# Cymbals.net
KiCad netlist of a schematic drawn in EAGLE
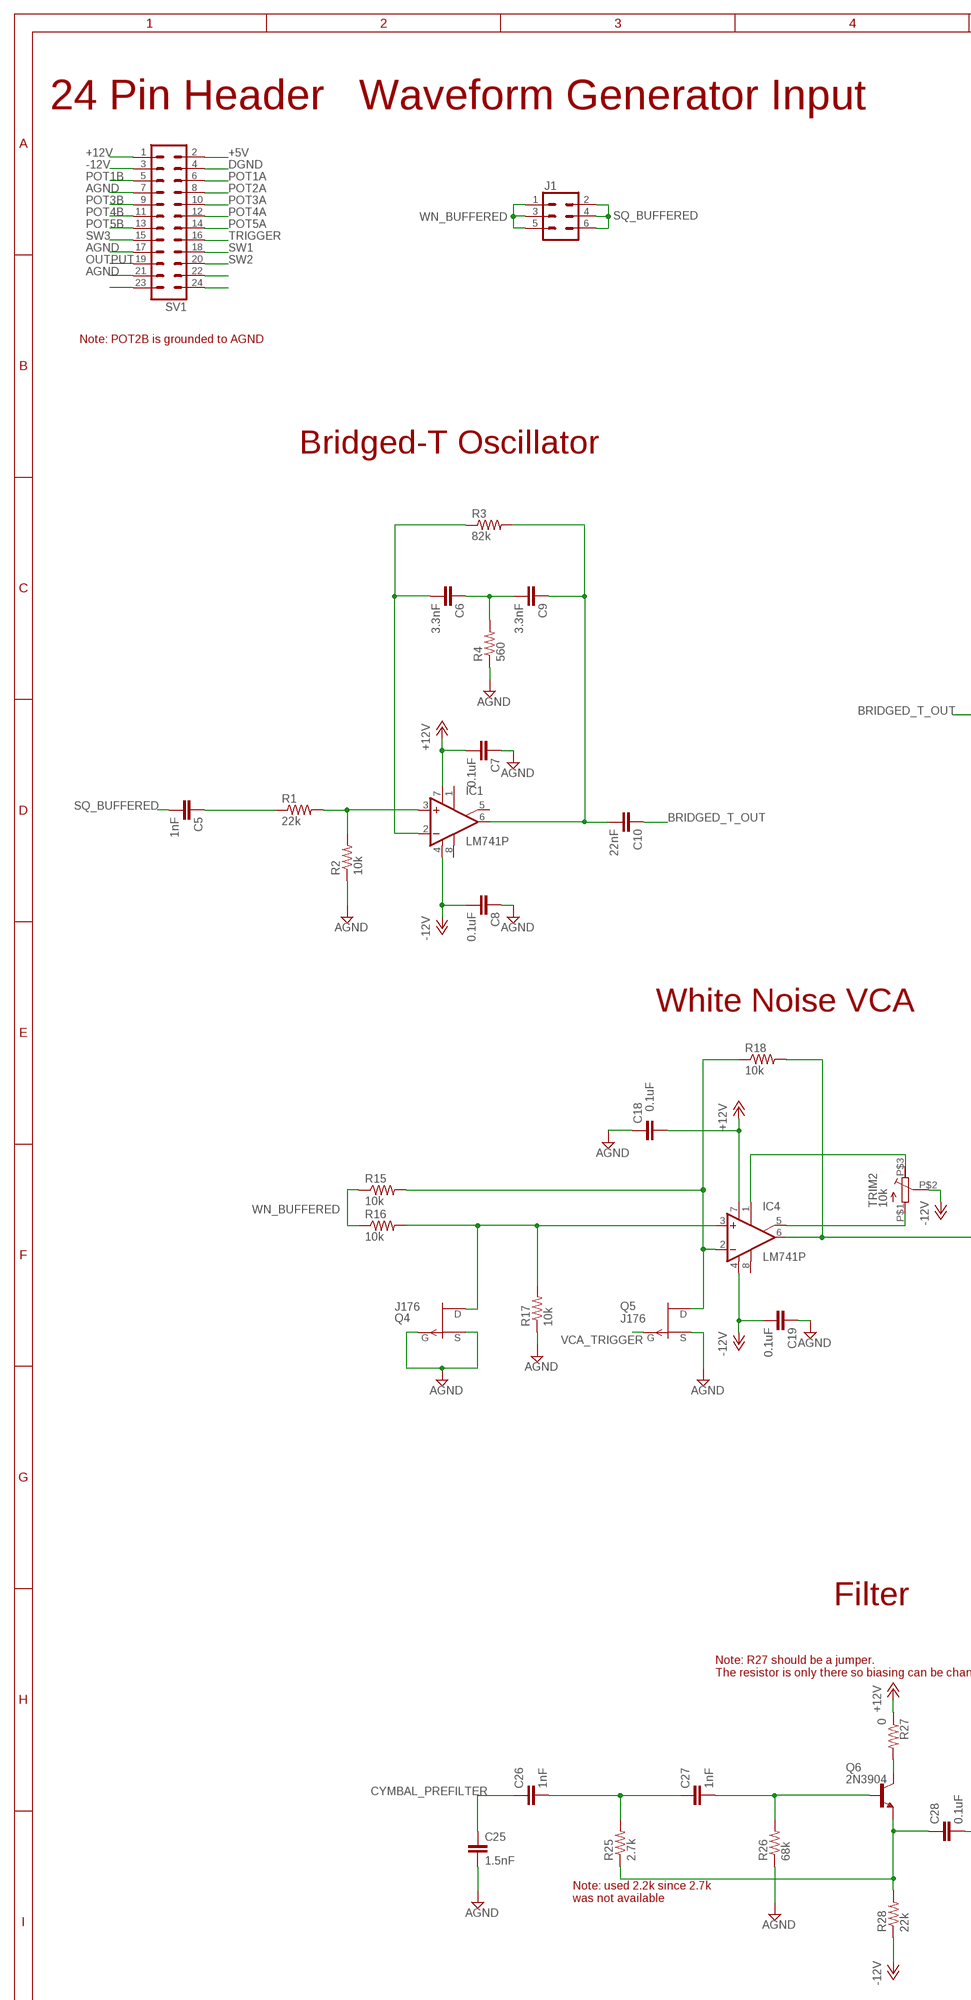
[diagram p0: schematic, sheet 1, part 1 of 2]
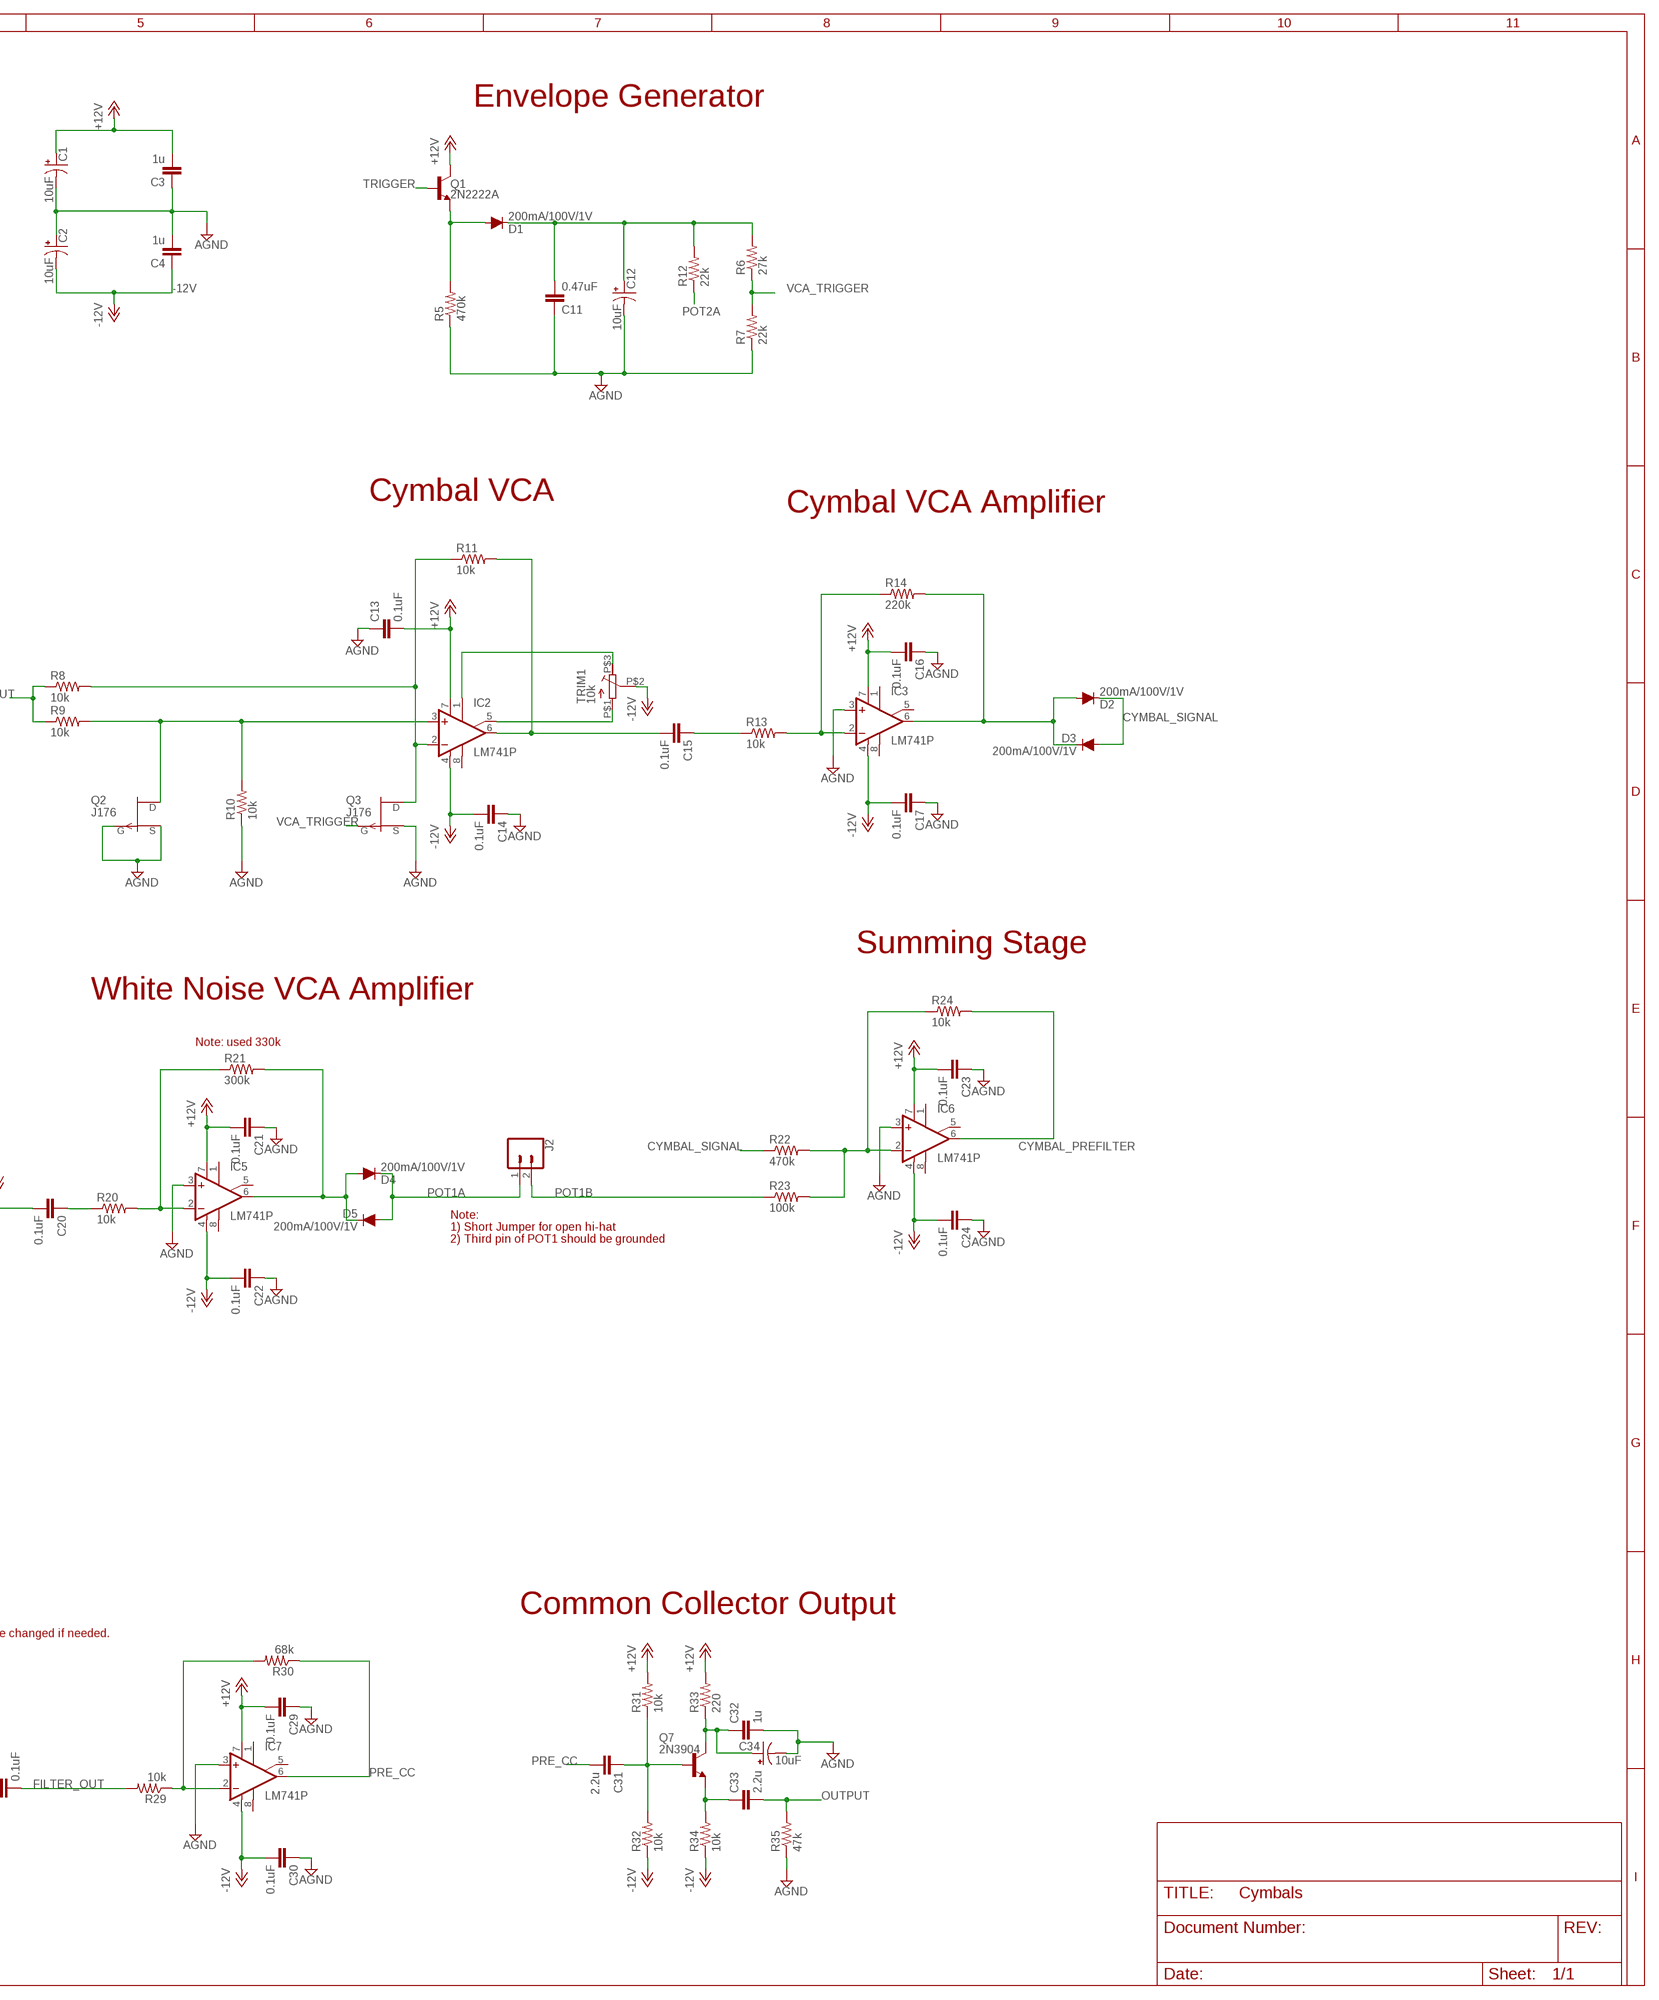
[diagram p1: schematic, sheet 1, part 2 of 2]

(export (version "E")
  (design (tool "Eeschema 10.0.6"))
  (components
    (comp (ref "C1")
      (value "10uF")
      (footprint "eagle-import:E2,5-6")
      (libsource (lib "eagle-import") (part "CPOL-USE2.5-6"))
    )
    (comp (ref "C2")
      (value "10uF")
      (footprint "eagle-import:E2,5-6")
      (libsource (lib "eagle-import") (part "CPOL-USE2.5-6"))
    )
    (comp (ref "C3")
      (value "1u")
      (footprint "eagle-import:C050-024X044")
      (libsource (lib "eagle-import") (part "C-EU050-024X044"))
    )
    (comp (ref "C4")
      (value "1u")
      (footprint "eagle-import:C050-024X044")
      (libsource (lib "eagle-import") (part "C-EU050-024X044"))
    )
    (comp (ref "C5")
      (value "1nF")
      (footprint "eagle-import:C050-024X044")
      (libsource (lib "eagle-import") (part "C-EU050-024X044"))
    )
    (comp (ref "C6")
      (value "3.3nF")
      (footprint "eagle-import:C050-024X044")
      (libsource (lib "eagle-import") (part "C-EU050-024X044"))
    )
    (comp (ref "C7")
      (value "0.1uF")
      (footprint "eagle-import:C050-024X044")
      (libsource (lib "eagle-import") (part "C-EU050-024X044"))
    )
    (comp (ref "C8")
      (value "0.1uF")
      (footprint "eagle-import:C050-024X044")
      (libsource (lib "eagle-import") (part "C-EU050-024X044"))
    )
    (comp (ref "C9")
      (value "3.3nF")
      (footprint "eagle-import:C050-024X044")
      (libsource (lib "eagle-import") (part "C-EU050-024X044"))
    )
    (comp (ref "C10")
      (value "22nF")
      (footprint "eagle-import:C050-024X044")
      (libsource (lib "eagle-import") (part "C-EU050-024X044"))
    )
    (comp (ref "C11")
      (value "0.47uF")
      (footprint "eagle-import:C050-024X044")
      (libsource (lib "eagle-import") (part "C-EU050-024X044"))
    )
    (comp (ref "C12")
      (value "10uF")
      (footprint "eagle-import:E2,5-6")
      (libsource (lib "eagle-import") (part "CPOL-USE2.5-6"))
    )
    (comp (ref "C13")
      (value "0.1uF")
      (footprint "eagle-import:C050-024X044")
      (libsource (lib "eagle-import") (part "C-EU050-024X044"))
    )
    (comp (ref "C14")
      (value "0.1uF")
      (footprint "eagle-import:C050-024X044")
      (libsource (lib "eagle-import") (part "C-EU050-024X044"))
    )
    (comp (ref "C15")
      (value "0.1uF")
      (footprint "eagle-import:C050-024X044")
      (libsource (lib "eagle-import") (part "C-EU050-024X044"))
    )
    (comp (ref "C16")
      (value "0.1uF")
      (footprint "eagle-import:C050-024X044")
      (libsource (lib "eagle-import") (part "C-EU050-024X044"))
    )
    (comp (ref "C17")
      (value "0.1uF")
      (footprint "eagle-import:C050-024X044")
      (libsource (lib "eagle-import") (part "C-EU050-024X044"))
    )
    (comp (ref "C18")
      (value "0.1uF")
      (footprint "eagle-import:C050-024X044")
      (libsource (lib "eagle-import") (part "C-EU050-024X044"))
    )
    (comp (ref "C19")
      (value "0.1uF")
      (footprint "eagle-import:C050-024X044")
      (libsource (lib "eagle-import") (part "C-EU050-024X044"))
    )
    (comp (ref "C20")
      (value "0.1uF")
      (footprint "eagle-import:C050-024X044")
      (libsource (lib "eagle-import") (part "C-EU050-024X044"))
    )
    (comp (ref "C21")
      (value "0.1uF")
      (footprint "eagle-import:C050-024X044")
      (libsource (lib "eagle-import") (part "C-EU050-024X044"))
    )
    (comp (ref "C22")
      (value "0.1uF")
      (footprint "eagle-import:C050-024X044")
      (libsource (lib "eagle-import") (part "C-EU050-024X044"))
    )
    (comp (ref "C23")
      (value "0.1uF")
      (footprint "eagle-import:C050-024X044")
      (libsource (lib "eagle-import") (part "C-EU050-024X044"))
    )
    (comp (ref "C24")
      (value "0.1uF")
      (footprint "eagle-import:C050-024X044")
      (libsource (lib "eagle-import") (part "C-EU050-024X044"))
    )
    (comp (ref "C25")
      (value "1.5nF")
      (footprint "eagle-import:C050-024X044")
      (libsource (lib "eagle-import") (part "C-EU050-024X044"))
    )
    (comp (ref "C26")
      (value "1nF")
      (footprint "eagle-import:C050-024X044")
      (libsource (lib "eagle-import") (part "C-EU050-024X044"))
    )
    (comp (ref "C27")
      (value "1nF")
      (footprint "eagle-import:C050-024X044")
      (libsource (lib "eagle-import") (part "C-EU050-024X044"))
    )
    (comp (ref "C28")
      (value "0.1uF")
      (footprint "eagle-import:C050-024X044")
      (libsource (lib "eagle-import") (part "C-EU050-024X044"))
    )
    (comp (ref "C29")
      (value "0.1uF")
      (footprint "eagle-import:C050-024X044")
      (libsource (lib "eagle-import") (part "C-EU050-024X044"))
    )
    (comp (ref "C30")
      (value "0.1uF")
      (footprint "eagle-import:C050-024X044")
      (libsource (lib "eagle-import") (part "C-EU050-024X044"))
    )
    (comp (ref "C31")
      (value "2.2u")
      (footprint "eagle-import:C050-024X044")
      (libsource (lib "eagle-import") (part "C-EU050-024X044"))
    )
    (comp (ref "C32")
      (value "1u")
      (footprint "eagle-import:C050-024X044")
      (libsource (lib "eagle-import") (part "C-EU050-024X044"))
    )
    (comp (ref "C33")
      (value "2.2u")
      (footprint "eagle-import:C050-024X044")
      (libsource (lib "eagle-import") (part "C-EU050-024X044"))
    )
    (comp (ref "C34")
      (value "10uF")
      (footprint "eagle-import:E2,5-6")
      (libsource (lib "eagle-import") (part "CPOL-USE2.5-6"))
    )
    (comp (ref "D1")
      (value "200mA/100V/1V")
      (footprint "eagle-import:DIODE-1N4148")
      (libsource (lib "eagle-import") (part "DIODE-1N4148"))
    )
    (comp (ref "D2")
      (value "200mA/100V/1V")
      (footprint "eagle-import:DIODE-1N4148")
      (libsource (lib "eagle-import") (part "DIODE-1N4148"))
    )
    (comp (ref "D3")
      (value "200mA/100V/1V")
      (footprint "eagle-import:DIODE-1N4148")
      (libsource (lib "eagle-import") (part "DIODE-1N4148"))
    )
    (comp (ref "D4")
      (value "200mA/100V/1V")
      (footprint "eagle-import:DIODE-1N4148")
      (libsource (lib "eagle-import") (part "DIODE-1N4148"))
    )
    (comp (ref "D5")
      (value "200mA/100V/1V")
      (footprint "eagle-import:DIODE-1N4148")
      (libsource (lib "eagle-import") (part "DIODE-1N4148"))
    )
    (comp (ref "IC1")
      (value "LM741P")
      (footprint "eagle-import:DIL08")
      (libsource (lib "eagle-import") (part "741PLM"))
    )
    (comp (ref "IC2")
      (value "LM741P")
      (footprint "eagle-import:DIL08")
      (libsource (lib "eagle-import") (part "741PLM"))
    )
    (comp (ref "IC3")
      (value "LM741P")
      (footprint "eagle-import:DIL08")
      (libsource (lib "eagle-import") (part "741PLM"))
    )
    (comp (ref "IC4")
      (value "LM741P")
      (footprint "eagle-import:DIL08")
      (libsource (lib "eagle-import") (part "741PLM"))
    )
    (comp (ref "IC5")
      (value "LM741P")
      (footprint "eagle-import:DIL08")
      (libsource (lib "eagle-import") (part "741PLM"))
    )
    (comp (ref "IC6")
      (value "LM741P")
      (footprint "eagle-import:DIL08")
      (libsource (lib "eagle-import") (part "741PLM"))
    )
    (comp (ref "IC7")
      (value "LM741P")
      (footprint "eagle-import:DIL08")
      (libsource (lib "eagle-import") (part "741PLM"))
    )
    (comp (ref "J1")
      (value "CONN_03X2NO_SILK")
      (footprint "eagle-import:2X3-NS")
      (libsource (lib "eagle-import") (part "CONN_03X2NO_SILK"))
    )
    (comp (ref "J2")
      (value "CONN_02")
      (footprint "eagle-import:1X02")
      (libsource (lib "eagle-import") (part "CONN_02"))
    )
    (comp (ref "Q1")
      (value "2N2222A")
      (footprint "eagle-import:TO-92")
      (libsource (lib "eagle-import") (part "TRANS_NPN-P2N2222A"))
    )
    (comp (ref "Q2")
      (value "J176")
      (footprint "eagle-import:TO-92")
      (libsource (lib "eagle-import") (part "J176"))
    )
    (comp (ref "Q3")
      (value "J176")
      (footprint "eagle-import:TO-92")
      (libsource (lib "eagle-import") (part "J176"))
    )
    (comp (ref "Q4")
      (value "J176")
      (footprint "eagle-import:TO-92")
      (libsource (lib "eagle-import") (part "J176"))
    )
    (comp (ref "Q5")
      (value "J176")
      (footprint "eagle-import:TO-92")
      (libsource (lib "eagle-import") (part "J176"))
    )
    (comp (ref "Q6")
      (value "2N3904")
      (footprint "eagle-import:TO92")
      (libsource (lib "eagle-import") (part "2N3904"))
    )
    (comp (ref "Q7")
      (value "2N3904")
      (footprint "eagle-import:TO92")
      (libsource (lib "eagle-import") (part "2N3904"))
    )
    (comp (ref "R1")
      (value "22k")
      (footprint "eagle-import:0207_7")
      (libsource (lib "eagle-import") (part "R-US_0207/7"))
    )
    (comp (ref "R2")
      (value "10k")
      (footprint "eagle-import:0207_7")
      (libsource (lib "eagle-import") (part "R-US_0207/7"))
    )
    (comp (ref "R3")
      (value "82k")
      (footprint "eagle-import:0207_7")
      (libsource (lib "eagle-import") (part "R-US_0207/7"))
    )
    (comp (ref "R4")
      (value "560")
      (footprint "eagle-import:0207_7")
      (libsource (lib "eagle-import") (part "R-US_0207/7"))
    )
    (comp (ref "R5")
      (value "470k")
      (footprint "eagle-import:0207_7")
      (libsource (lib "eagle-import") (part "R-US_0207/7"))
    )
    (comp (ref "R6")
      (value "27k")
      (footprint "eagle-import:0207_7")
      (libsource (lib "eagle-import") (part "R-US_0207/7"))
    )
    (comp (ref "R7")
      (value "22k")
      (footprint "eagle-import:0207_7")
      (libsource (lib "eagle-import") (part "R-US_0207/7"))
    )
    (comp (ref "R8")
      (value "10k")
      (footprint "eagle-import:0207_7")
      (libsource (lib "eagle-import") (part "R-US_0207/7"))
    )
    (comp (ref "R9")
      (value "10k")
      (footprint "eagle-import:0207_7")
      (libsource (lib "eagle-import") (part "R-US_0207/7"))
    )
    (comp (ref "R10")
      (value "10k")
      (footprint "eagle-import:0207_7")
      (libsource (lib "eagle-import") (part "R-US_0207/7"))
    )
    (comp (ref "R11")
      (value "10k")
      (footprint "eagle-import:0207_7")
      (libsource (lib "eagle-import") (part "R-US_0207/7"))
    )
    (comp (ref "R12")
      (value "22k")
      (footprint "eagle-import:0207_7")
      (libsource (lib "eagle-import") (part "R-US_0207/7"))
    )
    (comp (ref "R13")
      (value "10k")
      (footprint "eagle-import:0207_7")
      (libsource (lib "eagle-import") (part "R-US_0207/7"))
    )
    (comp (ref "R14")
      (value "220k")
      (footprint "eagle-import:0207_7")
      (libsource (lib "eagle-import") (part "R-US_0207/7"))
    )
    (comp (ref "R15")
      (value "10k")
      (footprint "eagle-import:0207_7")
      (libsource (lib "eagle-import") (part "R-US_0207/7"))
    )
    (comp (ref "R16")
      (value "10k")
      (footprint "eagle-import:0207_7")
      (libsource (lib "eagle-import") (part "R-US_0207/7"))
    )
    (comp (ref "R17")
      (value "10k")
      (footprint "eagle-import:0207_7")
      (libsource (lib "eagle-import") (part "R-US_0207/7"))
    )
    (comp (ref "R18")
      (value "10k")
      (footprint "eagle-import:0207_7")
      (libsource (lib "eagle-import") (part "R-US_0207/7"))
    )
    (comp (ref "R20")
      (value "10k")
      (footprint "eagle-import:0207_7")
      (libsource (lib "eagle-import") (part "R-US_0207/7"))
    )
    (comp (ref "R21")
      (value "300k")
      (footprint "eagle-import:0207_7")
      (libsource (lib "eagle-import") (part "R-US_0207/7"))
    )
    (comp (ref "R22")
      (value "470k")
      (footprint "eagle-import:0207_7")
      (libsource (lib "eagle-import") (part "R-US_0207/7"))
    )
    (comp (ref "R23")
      (value "100k")
      (footprint "eagle-import:0207_7")
      (libsource (lib "eagle-import") (part "R-US_0207/7"))
    )
    (comp (ref "R24")
      (value "10k")
      (footprint "eagle-import:0207_7")
      (libsource (lib "eagle-import") (part "R-US_0207/7"))
    )
    (comp (ref "R25")
      (value "2.7k")
      (footprint "eagle-import:0207_7")
      (libsource (lib "eagle-import") (part "R-US_0207/7"))
    )
    (comp (ref "R26")
      (value "68k")
      (footprint "eagle-import:0207_7")
      (libsource (lib "eagle-import") (part "R-US_0207/7"))
    )
    (comp (ref "R27")
      (value "0")
      (footprint "eagle-import:0207_7")
      (libsource (lib "eagle-import") (part "R-US_0207/7"))
    )
    (comp (ref "R28")
      (value "22k")
      (footprint "eagle-import:0207_7")
      (libsource (lib "eagle-import") (part "R-US_0207/7"))
    )
    (comp (ref "R29")
      (value "10k")
      (footprint "eagle-import:0207_7")
      (libsource (lib "eagle-import") (part "R-US_0207/7"))
    )
    (comp (ref "R30")
      (value "68k")
      (footprint "eagle-import:0207_7")
      (libsource (lib "eagle-import") (part "R-US_0207/7"))
    )
    (comp (ref "R31")
      (value "10k")
      (footprint "eagle-import:0207_7")
      (libsource (lib "eagle-import") (part "R-US_0207/7"))
    )
    (comp (ref "R32")
      (value "10k")
      (footprint "eagle-import:0207_7")
      (libsource (lib "eagle-import") (part "R-US_0207/7"))
    )
    (comp (ref "R33")
      (value "220")
      (footprint "eagle-import:0207_7")
      (libsource (lib "eagle-import") (part "R-US_0207/7"))
    )
    (comp (ref "R34")
      (value "10k")
      (footprint "eagle-import:0207_7")
      (libsource (lib "eagle-import") (part "R-US_0207/7"))
    )
    (comp (ref "R35")
      (value "47k")
      (footprint "eagle-import:0207_7")
      (libsource (lib "eagle-import") (part "R-US_0207/7"))
    )
    (comp (ref "SV1")
      (value "MA12-2")
      (footprint "eagle-import:MA12-2")
      (libsource (lib "eagle-import") (part "MA12-2"))
    )
    (comp (ref "TRIM1")
      (value "10k")
      (footprint "eagle-import:10K_TRIM")
      (libsource (lib "eagle-import") (part "10K_TRIMMER"))
    )
    (comp (ref "TRIM2")
      (value "10k")
      (footprint "eagle-import:10K_TRIM")
      (libsource (lib "eagle-import") (part "10K_TRIMMER"))
    )
  )
  (nets
    (net (code "1") (name "+12V") (class "Default")
      (node (ref "C1") (pin "+") (pinfunction "+_+") (pintype "passive"))
      (node (ref "C13") (pin "2") (pinfunction "2_2") (pintype "passive"))
      (node (ref "C16") (pin "2") (pinfunction "2_2") (pintype "passive"))
      (node (ref "C18") (pin "2") (pinfunction "2_2") (pintype "passive"))
      (node (ref "C21") (pin "2") (pinfunction "2_2") (pintype "passive"))
      (node (ref "C23") (pin "2") (pinfunction "2_2") (pintype "passive"))
      (node (ref "C29") (pin "2") (pinfunction "2_2") (pintype "passive"))
      (node (ref "C3") (pin "2") (pinfunction "2_2") (pintype "passive"))
      (node (ref "C7") (pin "2") (pinfunction "2_2") (pintype "passive"))
      (node (ref "IC1") (pin "7") (pinfunction "V+_7") (pintype "power_in"))
      (node (ref "IC2") (pin "7") (pinfunction "V+_7") (pintype "power_in"))
      (node (ref "IC3") (pin "7") (pinfunction "V+_7") (pintype "power_in"))
      (node (ref "IC4") (pin "7") (pinfunction "V+_7") (pintype "power_in"))
      (node (ref "IC5") (pin "7") (pinfunction "V+_7") (pintype "power_in"))
      (node (ref "IC6") (pin "7") (pinfunction "V+_7") (pintype "power_in"))
      (node (ref "IC7") (pin "7") (pinfunction "V+_7") (pintype "power_in"))
      (node (ref "Q1") (pin "1") (pinfunction "C_1") (pintype "passive"))
      (node (ref "R27") (pin "1") (pinfunction "1_1") (pintype "passive"))
      (node (ref "R31") (pin "2") (pinfunction "2_2") (pintype "passive"))
      (node (ref "R33") (pin "2") (pinfunction "2_2") (pintype "passive"))
      (node (ref "SV1") (pin "1") (pinfunction "1_1") (pintype "passive"))
    )
    (net (code "2") (name "-12V") (class "Default")
      (node (ref "C14") (pin "2") (pinfunction "2_2") (pintype "passive"))
      (node (ref "C17") (pin "2") (pinfunction "2_2") (pintype "passive"))
      (node (ref "C19") (pin "2") (pinfunction "2_2") (pintype "passive"))
      (node (ref "C2") (pin "-") (pinfunction "-_-") (pintype "passive"))
      (node (ref "C22") (pin "2") (pinfunction "2_2") (pintype "passive"))
      (node (ref "C24") (pin "2") (pinfunction "2_2") (pintype "passive"))
      (node (ref "C30") (pin "2") (pinfunction "2_2") (pintype "passive"))
      (node (ref "C4") (pin "1") (pinfunction "1_1") (pintype "passive"))
      (node (ref "C8") (pin "2") (pinfunction "2_2") (pintype "passive"))
      (node (ref "IC1") (pin "4") (pinfunction "V-_4") (pintype "power_in"))
      (node (ref "IC2") (pin "4") (pinfunction "V-_4") (pintype "power_in"))
      (node (ref "IC3") (pin "4") (pinfunction "V-_4") (pintype "power_in"))
      (node (ref "IC4") (pin "4") (pinfunction "V-_4") (pintype "power_in"))
      (node (ref "IC5") (pin "4") (pinfunction "V-_4") (pintype "power_in"))
      (node (ref "IC6") (pin "4") (pinfunction "V-_4") (pintype "power_in"))
      (node (ref "IC7") (pin "4") (pinfunction "V-_4") (pintype "power_in"))
      (node (ref "R28") (pin "1") (pinfunction "1_1") (pintype "passive"))
      (node (ref "R32") (pin "1") (pinfunction "1_1") (pintype "passive"))
      (node (ref "R34") (pin "1") (pinfunction "1_1") (pintype "passive"))
      (node (ref "SV1") (pin "3") (pinfunction "3_3") (pintype "passive"))
      (node (ref "TRIM1") (pin "P$2") (pinfunction "S_P$2") (pintype "passive"))
      (node (ref "TRIM2") (pin "P$2") (pinfunction "S_P$2") (pintype "passive"))
    )
    (net (code "3") (name "/+5V") (class "Default")
      (node (ref "SV1") (pin "2") (pinfunction "2_2") (pintype "passive"))
    )
    (net (code "4") (name "/BRIDGED_T_OUT") (class "Default")
      (node (ref "C10") (pin "1") (pinfunction "1_1") (pintype "passive"))
      (node (ref "R8") (pin "1") (pinfunction "1_1") (pintype "passive"))
      (node (ref "R9") (pin "1") (pinfunction "1_1") (pintype "passive"))
    )
    (net (code "5") (name "/CYMBAL_PREFILTER") (class "Default")
      (node (ref "C25") (pin "1") (pinfunction "1_1") (pintype "passive"))
      (node (ref "C26") (pin "1") (pinfunction "1_1") (pintype "passive"))
      (node (ref "IC6") (pin "6") (pinfunction "OUT_6") (pintype "output"))
      (node (ref "R24") (pin "2") (pinfunction "2_2") (pintype "passive"))
    )
    (net (code "6") (name "/CYMBAL_SIGNAL") (class "Default")
      (node (ref "D2") (pin "C") (pinfunction "C_C") (pintype "passive"))
      (node (ref "D3") (pin "A") (pinfunction "A_A") (pintype "passive"))
      (node (ref "R22") (pin "1") (pinfunction "1_1") (pintype "passive"))
    )
    (net (code "7") (name "/DGND") (class "Default")
      (node (ref "SV1") (pin "4") (pinfunction "4_4") (pintype "passive"))
    )
    (net (code "8") (name "/FILTER_OUT") (class "Default")
      (node (ref "C28") (pin "2") (pinfunction "2_2") (pintype "passive"))
      (node (ref "R29") (pin "2") (pinfunction "2_2") (pintype "passive"))
    )
    (net (code "9") (name "/OUTPUT") (class "Default")
      (node (ref "C33") (pin "2") (pinfunction "2_2") (pintype "passive"))
      (node (ref "R35") (pin "2") (pinfunction "2_2") (pintype "passive"))
      (node (ref "SV1") (pin "19") (pinfunction "19_19") (pintype "passive"))
    )
    (net (code "10") (name "/POT1A") (class "Default")
      (node (ref "D4") (pin "C") (pinfunction "C_C") (pintype "passive"))
      (node (ref "D5") (pin "A") (pinfunction "A_A") (pintype "passive"))
      (node (ref "J2") (pin "1") (pinfunction "1_1") (pintype "passive"))
      (node (ref "SV1") (pin "6") (pinfunction "6_6") (pintype "passive"))
    )
    (net (code "11") (name "/POT1B") (class "Default")
      (node (ref "J2") (pin "2") (pinfunction "2_2") (pintype "passive"))
      (node (ref "R23") (pin "1") (pinfunction "1_1") (pintype "passive"))
      (node (ref "SV1") (pin "5") (pinfunction "5_5") (pintype "passive"))
    )
    (net (code "12") (name "/POT2A") (class "Default")
      (node (ref "R12") (pin "1") (pinfunction "1_1") (pintype "passive"))
      (node (ref "SV1") (pin "8") (pinfunction "8_8") (pintype "passive"))
    )
    (net (code "13") (name "/POT3A") (class "Default")
      (node (ref "SV1") (pin "10") (pinfunction "10_10") (pintype "passive"))
    )
    (net (code "14") (name "/POT3B") (class "Default")
      (node (ref "SV1") (pin "9") (pinfunction "9_9") (pintype "passive"))
    )
    (net (code "15") (name "/POT4A") (class "Default")
      (node (ref "SV1") (pin "12") (pinfunction "12_12") (pintype "passive"))
    )
    (net (code "16") (name "/POT4B") (class "Default")
      (node (ref "SV1") (pin "11") (pinfunction "11_11") (pintype "passive"))
    )
    (net (code "17") (name "/POT5A") (class "Default")
      (node (ref "SV1") (pin "14") (pinfunction "14_14") (pintype "passive"))
    )
    (net (code "18") (name "/POT5B") (class "Default")
      (node (ref "SV1") (pin "13") (pinfunction "13_13") (pintype "passive"))
    )
    (net (code "19") (name "/PRE_CC") (class "Default")
      (node (ref "C31") (pin "2") (pinfunction "2_2") (pintype "passive"))
      (node (ref "IC7") (pin "6") (pinfunction "OUT_6") (pintype "output"))
      (node (ref "R30") (pin "1") (pinfunction "1_1") (pintype "passive"))
    )
    (net (code "20") (name "/SQ_BUFFERED") (class "Default")
      (node (ref "C5") (pin "2") (pinfunction "2_2") (pintype "passive"))
      (node (ref "J1") (pin "2") (pinfunction "2_2") (pintype "bidirectional"))
      (node (ref "J1") (pin "4") (pinfunction "4_4") (pintype "bidirectional"))
      (node (ref "J1") (pin "6") (pinfunction "6_6") (pintype "bidirectional"))
    )
    (net (code "21") (name "/SW1") (class "Default")
      (node (ref "SV1") (pin "18") (pinfunction "18_18") (pintype "passive"))
    )
    (net (code "22") (name "/SW2") (class "Default")
      (node (ref "SV1") (pin "20") (pinfunction "20_20") (pintype "passive"))
    )
    (net (code "23") (name "/SW3") (class "Default")
      (node (ref "SV1") (pin "15") (pinfunction "15_15") (pintype "passive"))
    )
    (net (code "24") (name "/TRIGGER") (class "Default")
      (node (ref "Q1") (pin "2") (pinfunction "B_2") (pintype "passive"))
      (node (ref "SV1") (pin "16") (pinfunction "16_16") (pintype "passive"))
    )
    (net (code "25") (name "/VCA_TRIGGER") (class "Default")
      (node (ref "Q3") (pin "2") (pinfunction "G_2") (pintype "passive"))
      (node (ref "Q5") (pin "2") (pinfunction "G_2") (pintype "passive"))
      (node (ref "R6") (pin "1") (pinfunction "1_1") (pintype "passive"))
      (node (ref "R7") (pin "2") (pinfunction "2_2") (pintype "passive"))
    )
    (net (code "26") (name "/WN_BUFFERED") (class "Default")
      (node (ref "J1") (pin "1") (pinfunction "1_1") (pintype "bidirectional"))
      (node (ref "J1") (pin "3") (pinfunction "3_3") (pintype "bidirectional"))
      (node (ref "J1") (pin "5") (pinfunction "5_5") (pintype "bidirectional"))
      (node (ref "R15") (pin "1") (pinfunction "1_1") (pintype "passive"))
      (node (ref "R16") (pin "1") (pinfunction "1_1") (pintype "passive"))
    )
    (net (code "27") (name "AGND") (class "Default")
      (node (ref "C1") (pin "-") (pinfunction "-_-") (pintype "passive"))
      (node (ref "C11") (pin "1") (pinfunction "1_1") (pintype "passive"))
      (node (ref "C12") (pin "-") (pinfunction "-_-") (pintype "passive"))
      (node (ref "C13") (pin "1") (pinfunction "1_1") (pintype "passive"))
      (node (ref "C14") (pin "1") (pinfunction "1_1") (pintype "passive"))
      (node (ref "C16") (pin "1") (pinfunction "1_1") (pintype "passive"))
      (node (ref "C17") (pin "1") (pinfunction "1_1") (pintype "passive"))
      (node (ref "C18") (pin "1") (pinfunction "1_1") (pintype "passive"))
      (node (ref "C19") (pin "1") (pinfunction "1_1") (pintype "passive"))
      (node (ref "C2") (pin "+") (pinfunction "+_+") (pintype "passive"))
      (node (ref "C21") (pin "1") (pinfunction "1_1") (pintype "passive"))
      (node (ref "C22") (pin "1") (pinfunction "1_1") (pintype "passive"))
      (node (ref "C23") (pin "1") (pinfunction "1_1") (pintype "passive"))
      (node (ref "C24") (pin "1") (pinfunction "1_1") (pintype "passive"))
      (node (ref "C25") (pin "2") (pinfunction "2_2") (pintype "passive"))
      (node (ref "C29") (pin "1") (pinfunction "1_1") (pintype "passive"))
      (node (ref "C3") (pin "1") (pinfunction "1_1") (pintype "passive"))
      (node (ref "C30") (pin "1") (pinfunction "1_1") (pintype "passive"))
      (node (ref "C32") (pin "2") (pinfunction "2_2") (pintype "passive"))
      (node (ref "C34") (pin "-") (pinfunction "-_-") (pintype "passive"))
      (node (ref "C4") (pin "2") (pinfunction "2_2") (pintype "passive"))
      (node (ref "C7") (pin "1") (pinfunction "1_1") (pintype "passive"))
      (node (ref "C8") (pin "1") (pinfunction "1_1") (pintype "passive"))
      (node (ref "IC3") (pin "3") (pinfunction "+IN_3") (pintype "input"))
      (node (ref "IC5") (pin "3") (pinfunction "+IN_3") (pintype "input"))
      (node (ref "IC6") (pin "3") (pinfunction "+IN_3") (pintype "input"))
      (node (ref "IC7") (pin "3") (pinfunction "+IN_3") (pintype "input"))
      (node (ref "Q2") (pin "2") (pinfunction "G_2") (pintype "passive"))
      (node (ref "Q2") (pin "3") (pinfunction "S_3") (pintype "passive"))
      (node (ref "Q3") (pin "3") (pinfunction "S_3") (pintype "passive"))
      (node (ref "Q4") (pin "2") (pinfunction "G_2") (pintype "passive"))
      (node (ref "Q4") (pin "3") (pinfunction "S_3") (pintype "passive"))
      (node (ref "Q5") (pin "3") (pinfunction "S_3") (pintype "passive"))
      (node (ref "R10") (pin "1") (pinfunction "1_1") (pintype "passive"))
      (node (ref "R17") (pin "1") (pinfunction "1_1") (pintype "passive"))
      (node (ref "R2") (pin "1") (pinfunction "1_1") (pintype "passive"))
      (node (ref "R26") (pin "1") (pinfunction "1_1") (pintype "passive"))
      (node (ref "R35") (pin "1") (pinfunction "1_1") (pintype "passive"))
      (node (ref "R4") (pin "1") (pinfunction "1_1") (pintype "passive"))
      (node (ref "R5") (pin "1") (pinfunction "1_1") (pintype "passive"))
      (node (ref "R7") (pin "1") (pinfunction "1_1") (pintype "passive"))
      (node (ref "SV1") (pin "17") (pinfunction "17_17") (pintype "passive"))
      (node (ref "SV1") (pin "21") (pinfunction "21_21") (pintype "passive"))
      (node (ref "SV1") (pin "7") (pinfunction "7_7") (pintype "passive"))
    )
    (net (code "28") (name "Net-(C5-Pad1)") (class "Default")
      (node (ref "C5") (pin "1") (pinfunction "1_1") (pintype "passive"))
      (node (ref "R1") (pin "1") (pinfunction "1_1") (pintype "passive"))
    )
    (net (code "29") (name "Net-(C6-Pad1)") (class "Default")
      (node (ref "C6") (pin "1") (pinfunction "1_1") (pintype "passive"))
      (node (ref "C9") (pin "2") (pinfunction "2_2") (pintype "passive"))
      (node (ref "R4") (pin "2") (pinfunction "2_2") (pintype "passive"))
    )
    (net (code "30") (name "Net-(C11-Pad2)") (class "Default")
      (node (ref "C11") (pin "2") (pinfunction "2_2") (pintype "passive"))
      (node (ref "C12") (pin "+") (pinfunction "+_+") (pintype "passive"))
      (node (ref "D1") (pin "C") (pinfunction "C_C") (pintype "passive"))
      (node (ref "R12") (pin "2") (pinfunction "2_2") (pintype "passive"))
      (node (ref "R6") (pin "2") (pinfunction "2_2") (pintype "passive"))
    )
    (net (code "31") (name "Net-(C15-Pad1)") (class "Default")
      (node (ref "C15") (pin "1") (pinfunction "1_1") (pintype "passive"))
      (node (ref "R13") (pin "1") (pinfunction "1_1") (pintype "passive"))
    )
    (net (code "32") (name "Net-(C20-Pad1)") (class "Default")
      (node (ref "C20") (pin "1") (pinfunction "1_1") (pintype "passive"))
      (node (ref "R20") (pin "1") (pinfunction "1_1") (pintype "passive"))
    )
    (net (code "33") (name "Net-(C26-Pad2)") (class "Default")
      (node (ref "C26") (pin "2") (pinfunction "2_2") (pintype "passive"))
      (node (ref "C27") (pin "1") (pinfunction "1_1") (pintype "passive"))
      (node (ref "R25") (pin "2") (pinfunction "2_2") (pintype "passive"))
    )
    (net (code "34") (name "Net-(IC1-+IN)") (class "Default")
      (node (ref "IC1") (pin "3") (pinfunction "+IN_3") (pintype "input"))
      (node (ref "R1") (pin "2") (pinfunction "2_2") (pintype "passive"))
      (node (ref "R2") (pin "2") (pinfunction "2_2") (pintype "passive"))
    )
    (net (code "35") (name "Net-(IC1--IN)") (class "Default")
      (node (ref "C6") (pin "2") (pinfunction "2_2") (pintype "passive"))
      (node (ref "IC1") (pin "2") (pinfunction "-IN_2") (pintype "input"))
      (node (ref "R3") (pin "1") (pinfunction "1_1") (pintype "passive"))
    )
    (net (code "36") (name "Net-(IC1-OUT)") (class "Default")
      (node (ref "C10") (pin "2") (pinfunction "2_2") (pintype "passive"))
      (node (ref "C9") (pin "1") (pinfunction "1_1") (pintype "passive"))
      (node (ref "IC1") (pin "6") (pinfunction "OUT_6") (pintype "output"))
      (node (ref "R3") (pin "2") (pinfunction "2_2") (pintype "passive"))
    )
    (net (code "37") (name "Net-(IC2-+IN)") (class "Default")
      (node (ref "IC2") (pin "3") (pinfunction "+IN_3") (pintype "input"))
      (node (ref "Q2") (pin "1") (pinfunction "D_1") (pintype "passive"))
      (node (ref "R10") (pin "2") (pinfunction "2_2") (pintype "passive"))
      (node (ref "R9") (pin "2") (pinfunction "2_2") (pintype "passive"))
    )
    (net (code "38") (name "Net-(IC2--IN)") (class "Default")
      (node (ref "IC2") (pin "2") (pinfunction "-IN_2") (pintype "input"))
      (node (ref "Q3") (pin "1") (pinfunction "D_1") (pintype "passive"))
      (node (ref "R11") (pin "1") (pinfunction "1_1") (pintype "passive"))
      (node (ref "R8") (pin "2") (pinfunction "2_2") (pintype "passive"))
    )
    (net (code "39") (name "Net-(IC2-ON1)") (class "Default")
      (node (ref "IC2") (pin "1") (pinfunction "ON1_1") (pintype "passive"))
      (node (ref "TRIM1") (pin "P$3") (pinfunction "E_P$3") (pintype "passive"))
    )
    (net (code "40") (name "Net-(IC2-ON2)") (class "Default")
      (node (ref "IC2") (pin "5") (pinfunction "ON2_5") (pintype "passive"))
      (node (ref "TRIM1") (pin "P$1") (pinfunction "A_P$1") (pintype "passive"))
    )
    (net (code "41") (name "Net-(IC2-OUT)") (class "Default")
      (node (ref "C15") (pin "2") (pinfunction "2_2") (pintype "passive"))
      (node (ref "IC2") (pin "6") (pinfunction "OUT_6") (pintype "output"))
      (node (ref "R11") (pin "2") (pinfunction "2_2") (pintype "passive"))
    )
    (net (code "42") (name "Net-(IC3--IN)") (class "Default")
      (node (ref "IC3") (pin "2") (pinfunction "-IN_2") (pintype "input"))
      (node (ref "R13") (pin "2") (pinfunction "2_2") (pintype "passive"))
      (node (ref "R14") (pin "1") (pinfunction "1_1") (pintype "passive"))
    )
    (net (code "43") (name "Net-(IC3-OUT)") (class "Default")
      (node (ref "D2") (pin "A") (pinfunction "A_A") (pintype "passive"))
      (node (ref "D3") (pin "C") (pinfunction "C_C") (pintype "passive"))
      (node (ref "IC3") (pin "6") (pinfunction "OUT_6") (pintype "output"))
      (node (ref "R14") (pin "2") (pinfunction "2_2") (pintype "passive"))
    )
    (net (code "44") (name "Net-(IC4-+IN)") (class "Default")
      (node (ref "IC4") (pin "3") (pinfunction "+IN_3") (pintype "input"))
      (node (ref "Q4") (pin "1") (pinfunction "D_1") (pintype "passive"))
      (node (ref "R16") (pin "2") (pinfunction "2_2") (pintype "passive"))
      (node (ref "R17") (pin "2") (pinfunction "2_2") (pintype "passive"))
    )
    (net (code "45") (name "Net-(IC4--IN)") (class "Default")
      (node (ref "IC4") (pin "2") (pinfunction "-IN_2") (pintype "input"))
      (node (ref "Q5") (pin "1") (pinfunction "D_1") (pintype "passive"))
      (node (ref "R15") (pin "2") (pinfunction "2_2") (pintype "passive"))
      (node (ref "R18") (pin "1") (pinfunction "1_1") (pintype "passive"))
    )
    (net (code "46") (name "Net-(IC4-ON1)") (class "Default")
      (node (ref "IC4") (pin "1") (pinfunction "ON1_1") (pintype "passive"))
      (node (ref "TRIM2") (pin "P$3") (pinfunction "E_P$3") (pintype "passive"))
    )
    (net (code "47") (name "Net-(IC4-ON2)") (class "Default")
      (node (ref "IC4") (pin "5") (pinfunction "ON2_5") (pintype "passive"))
      (node (ref "TRIM2") (pin "P$1") (pinfunction "A_P$1") (pintype "passive"))
    )
    (net (code "48") (name "Net-(IC4-OUT)") (class "Default")
      (node (ref "C20") (pin "2") (pinfunction "2_2") (pintype "passive"))
      (node (ref "IC4") (pin "6") (pinfunction "OUT_6") (pintype "output"))
      (node (ref "R18") (pin "2") (pinfunction "2_2") (pintype "passive"))
    )
    (net (code "49") (name "Net-(IC5--IN)") (class "Default")
      (node (ref "IC5") (pin "2") (pinfunction "-IN_2") (pintype "input"))
      (node (ref "R20") (pin "2") (pinfunction "2_2") (pintype "passive"))
      (node (ref "R21") (pin "1") (pinfunction "1_1") (pintype "passive"))
    )
    (net (code "50") (name "Net-(IC5-OUT)") (class "Default")
      (node (ref "D4") (pin "A") (pinfunction "A_A") (pintype "passive"))
      (node (ref "D5") (pin "C") (pinfunction "C_C") (pintype "passive"))
      (node (ref "IC5") (pin "6") (pinfunction "OUT_6") (pintype "output"))
      (node (ref "R21") (pin "2") (pinfunction "2_2") (pintype "passive"))
    )
    (net (code "51") (name "Net-(IC6--IN)") (class "Default")
      (node (ref "IC6") (pin "2") (pinfunction "-IN_2") (pintype "input"))
      (node (ref "R22") (pin "2") (pinfunction "2_2") (pintype "passive"))
      (node (ref "R23") (pin "2") (pinfunction "2_2") (pintype "passive"))
      (node (ref "R24") (pin "1") (pinfunction "1_1") (pintype "passive"))
    )
    (net (code "52") (name "Net-(IC7--IN)") (class "Default")
      (node (ref "IC7") (pin "2") (pinfunction "-IN_2") (pintype "input"))
      (node (ref "R29") (pin "1") (pinfunction "1_1") (pintype "passive"))
      (node (ref "R30") (pin "2") (pinfunction "2_2") (pintype "passive"))
    )
    (net (code "53") (name "Net-(Q1-E)") (class "Default")
      (node (ref "D1") (pin "A") (pinfunction "A_A") (pintype "passive"))
      (node (ref "Q1") (pin "3") (pinfunction "E_3") (pintype "passive"))
      (node (ref "R5") (pin "2") (pinfunction "2_2") (pintype "passive"))
    )
    (net (code "54") (name "Net-(Q6-B)") (class "Default")
      (node (ref "C27") (pin "2") (pinfunction "2_2") (pintype "passive"))
      (node (ref "Q6") (pin "2") (pinfunction "B_2") (pintype "passive"))
      (node (ref "R26") (pin "2") (pinfunction "2_2") (pintype "passive"))
    )
    (net (code "55") (name "Net-(Q6-C)") (class "Default")
      (node (ref "Q6") (pin "1") (pinfunction "C_1") (pintype "passive"))
      (node (ref "R27") (pin "2") (pinfunction "2_2") (pintype "passive"))
    )
    (net (code "56") (name "Net-(Q6-E)") (class "Default")
      (node (ref "C28") (pin "1") (pinfunction "1_1") (pintype "passive"))
      (node (ref "Q6") (pin "3") (pinfunction "E_3") (pintype "passive"))
      (node (ref "R25") (pin "1") (pinfunction "1_1") (pintype "passive"))
      (node (ref "R28") (pin "2") (pinfunction "2_2") (pintype "passive"))
    )
    (net (code "57") (name "Net-(Q7-B)") (class "Default")
      (node (ref "C31") (pin "1") (pinfunction "1_1") (pintype "passive"))
      (node (ref "Q7") (pin "2") (pinfunction "B_2") (pintype "passive"))
      (node (ref "R31") (pin "1") (pinfunction "1_1") (pintype "passive"))
      (node (ref "R32") (pin "2") (pinfunction "2_2") (pintype "passive"))
    )
    (net (code "58") (name "Net-(Q7-C)") (class "Default")
      (node (ref "C32") (pin "1") (pinfunction "1_1") (pintype "passive"))
      (node (ref "C34") (pin "+") (pinfunction "+_+") (pintype "passive"))
      (node (ref "Q7") (pin "1") (pinfunction "C_1") (pintype "passive"))
      (node (ref "R33") (pin "1") (pinfunction "1_1") (pintype "passive"))
    )
    (net (code "59") (name "Net-(Q7-E)") (class "Default")
      (node (ref "C33") (pin "1") (pinfunction "1_1") (pintype "passive"))
      (node (ref "Q7") (pin "3") (pinfunction "E_3") (pintype "passive"))
      (node (ref "R34") (pin "2") (pinfunction "2_2") (pintype "passive"))
    )
    (net (code "60") (name "unconnected-(IC1-ON1-Pad1)") (class "Default")
      (node (ref "IC1") (pin "1") (pinfunction "ON1_1") (pintype "passive"))
    )
    (net (code "61") (name "unconnected-(IC1-ON2-Pad5)") (class "Default")
      (node (ref "IC1") (pin "5") (pinfunction "ON2_5") (pintype "passive"))
    )
    (net (code "62") (name "unconnected-(IC1-OPT-Pad8)") (class "Default")
      (node (ref "IC1") (pin "8") (pinfunction "OPT_8") (pintype "passive"))
    )
    (net (code "63") (name "unconnected-(IC2-OPT-Pad8)") (class "Default")
      (node (ref "IC2") (pin "8") (pinfunction "OPT_8") (pintype "passive"))
    )
    (net (code "64") (name "unconnected-(IC3-ON1-Pad1)") (class "Default")
      (node (ref "IC3") (pin "1") (pinfunction "ON1_1") (pintype "passive"))
    )
    (net (code "65") (name "unconnected-(IC3-ON2-Pad5)") (class "Default")
      (node (ref "IC3") (pin "5") (pinfunction "ON2_5") (pintype "passive"))
    )
    (net (code "66") (name "unconnected-(IC3-OPT-Pad8)") (class "Default")
      (node (ref "IC3") (pin "8") (pinfunction "OPT_8") (pintype "passive"))
    )
    (net (code "67") (name "unconnected-(IC4-OPT-Pad8)") (class "Default")
      (node (ref "IC4") (pin "8") (pinfunction "OPT_8") (pintype "passive"))
    )
    (net (code "68") (name "unconnected-(IC5-ON1-Pad1)") (class "Default")
      (node (ref "IC5") (pin "1") (pinfunction "ON1_1") (pintype "passive"))
    )
    (net (code "69") (name "unconnected-(IC5-ON2-Pad5)") (class "Default")
      (node (ref "IC5") (pin "5") (pinfunction "ON2_5") (pintype "passive"))
    )
    (net (code "70") (name "unconnected-(IC5-OPT-Pad8)") (class "Default")
      (node (ref "IC5") (pin "8") (pinfunction "OPT_8") (pintype "passive"))
    )
    (net (code "71") (name "unconnected-(IC6-ON1-Pad1)") (class "Default")
      (node (ref "IC6") (pin "1") (pinfunction "ON1_1") (pintype "passive"))
    )
    (net (code "72") (name "unconnected-(IC6-ON2-Pad5)") (class "Default")
      (node (ref "IC6") (pin "5") (pinfunction "ON2_5") (pintype "passive"))
    )
    (net (code "73") (name "unconnected-(IC6-OPT-Pad8)") (class "Default")
      (node (ref "IC6") (pin "8") (pinfunction "OPT_8") (pintype "passive"))
    )
    (net (code "74") (name "unconnected-(IC7-ON1-Pad1)") (class "Default")
      (node (ref "IC7") (pin "1") (pinfunction "ON1_1") (pintype "passive"))
    )
    (net (code "75") (name "unconnected-(IC7-ON2-Pad5)") (class "Default")
      (node (ref "IC7") (pin "5") (pinfunction "ON2_5") (pintype "passive"))
    )
    (net (code "76") (name "unconnected-(IC7-OPT-Pad8)") (class "Default")
      (node (ref "IC7") (pin "8") (pinfunction "OPT_8") (pintype "passive"))
    )
    (net (code "77") (name "unconnected-(SV1-Pad22)") (class "Default")
      (node (ref "SV1") (pin "22") (pinfunction "22_22") (pintype "passive"))
    )
    (net (code "78") (name "unconnected-(SV1-Pad23)") (class "Default")
      (node (ref "SV1") (pin "23") (pinfunction "23_23") (pintype "passive"))
    )
    (net (code "79") (name "unconnected-(SV1-Pad24)") (class "Default")
      (node (ref "SV1") (pin "24") (pinfunction "24_24") (pintype "passive"))
    )
  )
)
